# Toyota_AutoSwitch_Giraffe.net
KiCad netlist of a schematic drawn in EAGLE
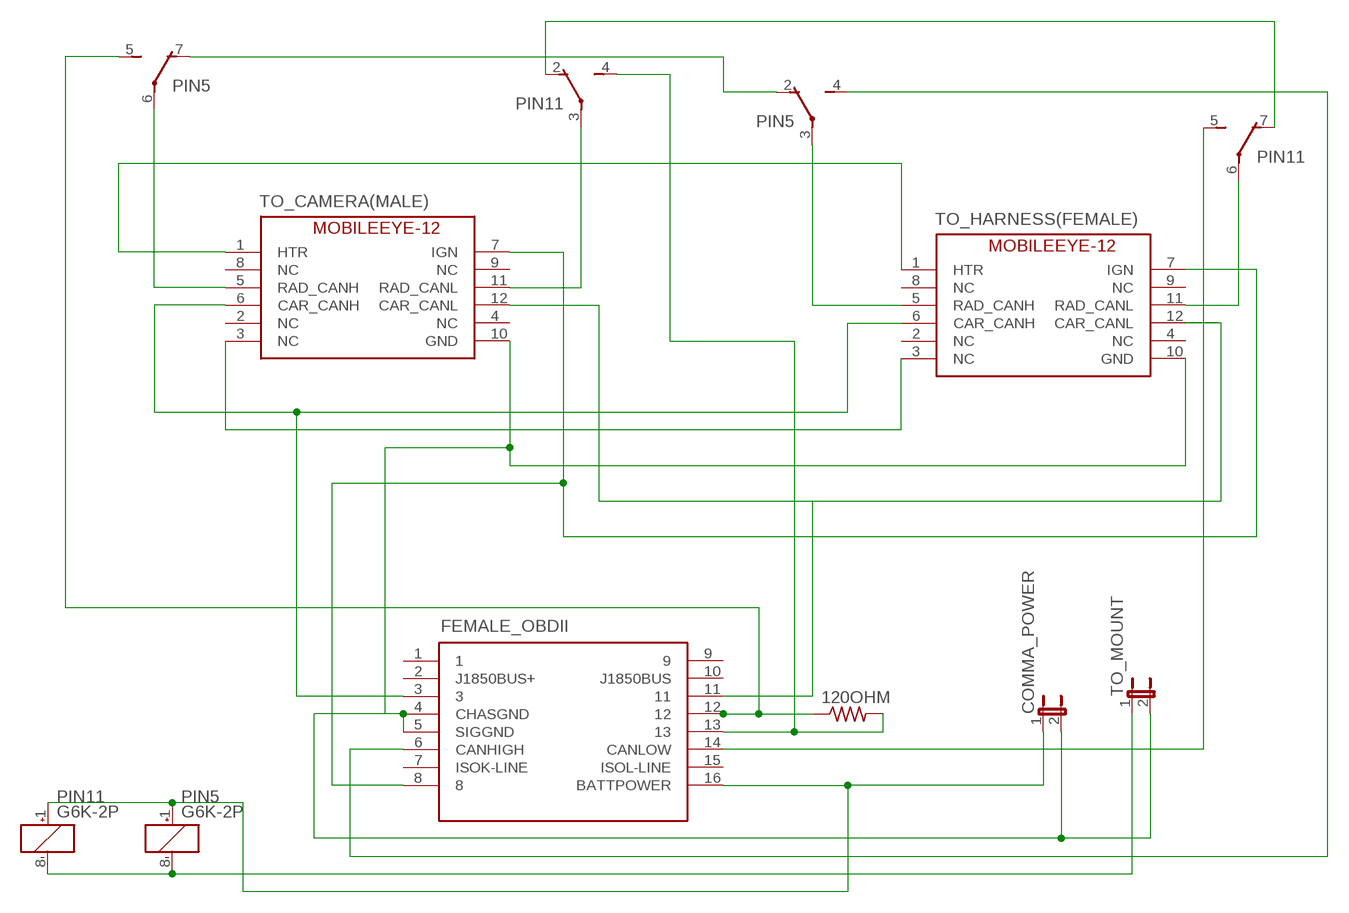
[diagram p0: schematic, sheet 1]

(export (version "E")
  (design (tool "Eeschema 10.0.6"))
  (components
    (comp (ref "120OHM")
      (value "R-US_0204/7")
      (footprint "eagle-import:0204_7")
      (libsource (lib "eagle-import") (part "R-US_0204/7"))
    )
    (comp (ref "COMMA_POWER")
      (value "JP1E")
      (footprint "eagle-import:JP1")
      (libsource (lib "eagle-import") (part "JP1E"))
    )
    (comp (ref "FEMALE_OBDII")
      (value "OBDIIFEMALE")
      (footprint "eagle-import:OBDII-FEMALE")
      (libsource (lib "eagle-import") (part "OBDIIFEMALE"))
    )
    (comp (ref "PIN5")
      (value "G6K-2P")
      (footprint "eagle-import:G6K-2P")
      (fields (field (name "MF") "OMRON COMPONENTS USA") (field (name "MPN") "G6K-2P DC3"))
      (libsource (lib "eagle-import") (part "G6K-2P"))
    )
    (comp (ref "PIN11")
      (value "G6K-2P")
      (footprint "eagle-import:G6K-2P")
      (fields (field (name "MF") "OMRON COMPONENTS USA") (field (name "MPN") "G6K-2P DC3"))
      (libsource (lib "eagle-import") (part "G6K-2P"))
    )
    (comp (ref "TO_CAMERA(MALE)")
      (value "MOBILEEYE-12FEMALE")
      (footprint "eagle-import:2X6-TE-FEMALE")
      (libsource (lib "eagle-import") (part "MOBILEEYE-12FEMALE"))
    )
    (comp (ref "TO_HARNESS(FEMALE)")
      (value "MOBILEEYE-12FEMALE")
      (footprint "eagle-import:2X6-TE-FEMALE")
      (libsource (lib "eagle-import") (part "MOBILEEYE-12FEMALE"))
    )
    (comp (ref "TO_MOUNT")
      (value "JP1E")
      (footprint "eagle-import:JP1")
      (libsource (lib "eagle-import") (part "JP1E"))
    )
  )
  (nets
    (net (code "1") (name "Net-(FEMALE_OBDII-BATTPOWER)") (class "Default")
      (node (ref "COMMA_POWER") (pin "1") (pinfunction "1_1") (pintype "passive"))
      (node (ref "FEMALE_OBDII") (pin "16") (pinfunction "BATTPOWER_16") (pintype "bidirectional"))
      (node (ref "PIN11") (pin "1") (pinfunction "+_1") (pintype "passive"))
      (node (ref "PIN5") (pin "1") (pinfunction "+_1") (pintype "passive"))
    )
    (net (code "2") (name "Net-(FEMALE_OBDII-CANHIGH)") (class "Default")
      (node (ref "FEMALE_OBDII") (pin "6") (pinfunction "CANHIGH_6") (pintype "bidirectional"))
      (node (ref "PIN5") (pin "4") (pinfunction "S_4") (pintype "passive"))
    )
    (net (code "3") (name "Net-(FEMALE_OBDII-CANLOW)") (class "Default")
      (node (ref "FEMALE_OBDII") (pin "14") (pinfunction "CANLOW_14") (pintype "bidirectional"))
      (node (ref "PIN11") (pin "5") (pinfunction "S_5") (pintype "passive"))
    )
    (net (code "4") (name "Net-(FEMALE_OBDII-CHASGND)") (class "Default")
      (node (ref "COMMA_POWER") (pin "2") (pinfunction "2_2") (pintype "passive"))
      (node (ref "FEMALE_OBDII") (pin "4") (pinfunction "CHASGND_4") (pintype "bidirectional"))
      (node (ref "FEMALE_OBDII") (pin "5") (pinfunction "SIGGND_5") (pintype "bidirectional"))
      (node (ref "TO_CAMERA(MALE)") (pin "10") (pinfunction "GND_10") (pintype "bidirectional"))
      (node (ref "TO_HARNESS(FEMALE)") (pin "10") (pinfunction "GND_10") (pintype "bidirectional"))
      (node (ref "TO_MOUNT") (pin "2") (pinfunction "2_2") (pintype "passive"))
    )
    (net (code "5") (name "Net-(PIN5B-O)") (class "Default")
      (node (ref "PIN5") (pin "2") (pinfunction "O_2") (pintype "passive"))
      (node (ref "PIN5") (pin "7") (pinfunction "O_7") (pintype "passive"))
    )
    (net (code "6") (name "Net-(PIN5B-P)") (class "Default")
      (node (ref "PIN5") (pin "3") (pinfunction "P_3") (pintype "passive"))
      (node (ref "TO_HARNESS(FEMALE)") (pin "5") (pinfunction "RAD_CANH_5") (pintype "bidirectional"))
    )
    (net (code "7") (name "Net-(PIN5C-P)") (class "Default")
      (node (ref "PIN5") (pin "6") (pinfunction "P_6") (pintype "passive"))
      (node (ref "TO_CAMERA(MALE)") (pin "5") (pinfunction "RAD_CANH_5") (pintype "bidirectional"))
    )
    (net (code "8") (name "Net-(PIN5C-S)") (class "Default")
      (node (ref "120OHM") (pin "1") (pinfunction "1_1") (pintype "passive"))
      (node (ref "FEMALE_OBDII") (pin "12") (pinfunction "12_12") (pintype "bidirectional"))
      (node (ref "PIN5") (pin "5") (pinfunction "S_5") (pintype "passive"))
    )
    (net (code "9") (name "Net-(PIN11A--)") (class "Default")
      (node (ref "PIN11") (pin "8") (pinfunction "-_8") (pintype "passive"))
      (node (ref "PIN5") (pin "8") (pinfunction "-_8") (pintype "passive"))
      (node (ref "TO_MOUNT") (pin "1") (pinfunction "1_1") (pintype "passive"))
    )
    (net (code "10") (name "Net-(PIN11B-O)") (class "Default")
      (node (ref "PIN11") (pin "2") (pinfunction "O_2") (pintype "passive"))
      (node (ref "PIN11") (pin "7") (pinfunction "O_7") (pintype "passive"))
    )
    (net (code "11") (name "Net-(PIN11B-P)") (class "Default")
      (node (ref "PIN11") (pin "3") (pinfunction "P_3") (pintype "passive"))
      (node (ref "TO_CAMERA(MALE)") (pin "11") (pinfunction "RAD_CANL_11") (pintype "bidirectional"))
    )
    (net (code "12") (name "Net-(PIN11B-S)") (class "Default")
      (node (ref "120OHM") (pin "2") (pinfunction "2_2") (pintype "passive"))
      (node (ref "FEMALE_OBDII") (pin "13") (pinfunction "13_13") (pintype "bidirectional"))
      (node (ref "PIN11") (pin "4") (pinfunction "S_4") (pintype "passive"))
    )
    (net (code "13") (name "Net-(PIN11C-P)") (class "Default")
      (node (ref "PIN11") (pin "6") (pinfunction "P_6") (pintype "passive"))
      (node (ref "TO_HARNESS(FEMALE)") (pin "11") (pinfunction "RAD_CANL_11") (pintype "bidirectional"))
    )
    (net (code "14") (name "Net-(TO_CAMERA(MALE)-CAR_CANH)") (class "Default")
      (node (ref "FEMALE_OBDII") (pin "3") (pinfunction "3_3") (pintype "bidirectional"))
      (node (ref "TO_CAMERA(MALE)") (pin "6") (pinfunction "CAR_CANH_6") (pintype "bidirectional"))
      (node (ref "TO_HARNESS(FEMALE)") (pin "6") (pinfunction "CAR_CANH_6") (pintype "bidirectional"))
    )
    (net (code "15") (name "Net-(TO_CAMERA(MALE)-CAR_CANL)") (class "Default")
      (node (ref "FEMALE_OBDII") (pin "11") (pinfunction "11_11") (pintype "bidirectional"))
      (node (ref "TO_CAMERA(MALE)") (pin "12") (pinfunction "CAR_CANL_12") (pintype "bidirectional"))
      (node (ref "TO_HARNESS(FEMALE)") (pin "12") (pinfunction "CAR_CANL_12") (pintype "bidirectional"))
    )
    (net (code "16") (name "Net-(TO_CAMERA(MALE)-HTR)") (class "Default")
      (node (ref "TO_CAMERA(MALE)") (pin "1") (pinfunction "HTR_1") (pintype "bidirectional"))
      (node (ref "TO_HARNESS(FEMALE)") (pin "1") (pinfunction "HTR_1") (pintype "bidirectional"))
    )
    (net (code "17") (name "Net-(TO_CAMERA(MALE)-IGN)") (class "Default")
      (node (ref "FEMALE_OBDII") (pin "8") (pinfunction "8_8") (pintype "bidirectional"))
      (node (ref "TO_CAMERA(MALE)") (pin "7") (pinfunction "IGN_7") (pintype "bidirectional"))
      (node (ref "TO_HARNESS(FEMALE)") (pin "7") (pinfunction "IGN_7") (pintype "bidirectional"))
    )
    (net (code "18") (name "Net-(TO_CAMERA(MALE)-NC-Pad3)") (class "Default")
      (node (ref "TO_CAMERA(MALE)") (pin "3") (pinfunction "NC_3") (pintype "bidirectional"))
      (node (ref "TO_HARNESS(FEMALE)") (pin "3") (pinfunction "NC_3") (pintype "bidirectional"))
    )
    (net (code "19") (name "unconnected-(FEMALE_OBDII-ISOK-LINE-Pad7)") (class "Default")
      (node (ref "FEMALE_OBDII") (pin "7") (pinfunction "ISOK-LINE_7") (pintype "bidirectional"))
    )
    (net (code "20") (name "unconnected-(FEMALE_OBDII-ISOL-LINE-Pad15)") (class "Default")
      (node (ref "FEMALE_OBDII") (pin "15") (pinfunction "ISOL-LINE_15") (pintype "bidirectional"))
    )
    (net (code "21") (name "unconnected-(FEMALE_OBDII-J1850BUS+-Pad2)") (class "Default")
      (node (ref "FEMALE_OBDII") (pin "2") (pinfunction "J1850BUS+_2") (pintype "bidirectional"))
    )
    (net (code "22") (name "unconnected-(FEMALE_OBDII-J1850BUS-Pad10)") (class "Default")
      (node (ref "FEMALE_OBDII") (pin "10") (pinfunction "J1850BUS_10") (pintype "bidirectional"))
    )
    (net (code "23") (name "unconnected-(FEMALE_OBDII-Pad1)") (class "Default")
      (node (ref "FEMALE_OBDII") (pin "1") (pinfunction "1_1") (pintype "bidirectional"))
    )
    (net (code "24") (name "unconnected-(FEMALE_OBDII-Pad9)") (class "Default")
      (node (ref "FEMALE_OBDII") (pin "9") (pinfunction "9_9") (pintype "bidirectional"))
    )
    (net (code "25") (name "unconnected-(TO_CAMERA(MALE)-NC-Pad2)") (class "Default")
      (node (ref "TO_CAMERA(MALE)") (pin "2") (pinfunction "NC_2") (pintype "bidirectional"))
    )
    (net (code "26") (name "unconnected-(TO_CAMERA(MALE)-NC-Pad4)") (class "Default")
      (node (ref "TO_CAMERA(MALE)") (pin "4") (pinfunction "NC_4") (pintype "bidirectional"))
    )
    (net (code "27") (name "unconnected-(TO_CAMERA(MALE)-NC-Pad8)") (class "Default")
      (node (ref "TO_CAMERA(MALE)") (pin "8") (pinfunction "NC_8") (pintype "bidirectional"))
    )
    (net (code "28") (name "unconnected-(TO_CAMERA(MALE)-NC-Pad9)") (class "Default")
      (node (ref "TO_CAMERA(MALE)") (pin "9") (pinfunction "NC_9") (pintype "bidirectional"))
    )
    (net (code "29") (name "unconnected-(TO_HARNESS(FEMALE)-NC-Pad2)") (class "Default")
      (node (ref "TO_HARNESS(FEMALE)") (pin "2") (pinfunction "NC_2") (pintype "bidirectional"))
    )
    (net (code "30") (name "unconnected-(TO_HARNESS(FEMALE)-NC-Pad4)") (class "Default")
      (node (ref "TO_HARNESS(FEMALE)") (pin "4") (pinfunction "NC_4") (pintype "bidirectional"))
    )
    (net (code "31") (name "unconnected-(TO_HARNESS(FEMALE)-NC-Pad8)") (class "Default")
      (node (ref "TO_HARNESS(FEMALE)") (pin "8") (pinfunction "NC_8") (pintype "bidirectional"))
    )
    (net (code "32") (name "unconnected-(TO_HARNESS(FEMALE)-NC-Pad9)") (class "Default")
      (node (ref "TO_HARNESS(FEMALE)") (pin "9") (pinfunction "NC_9") (pintype "bidirectional"))
    )
  )
)
